# h_bridge.net
KiCad netlist of a schematic drawn in EAGLE
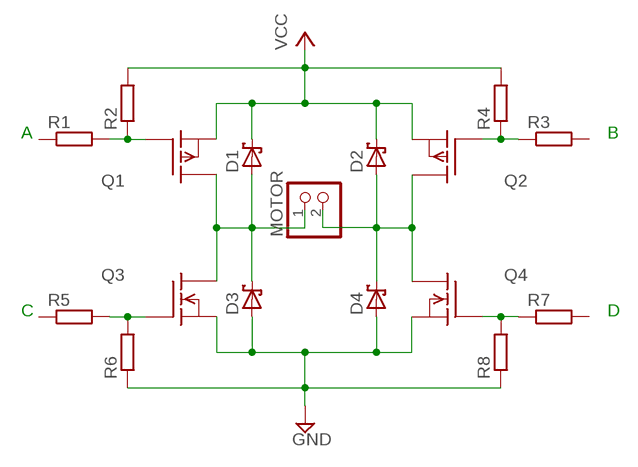
[diagram p0: schematic, sheet 1]

(export (version "E")
  (design (tool "Eeschema 10.0.6"))
  (components
    (comp (ref "D1")
      (value "1N6267A")
      (footprint "eagle-import:C4111-15")
      (libsource (lib "eagle-import") (part "1N6267A"))
    )
    (comp (ref "D2")
      (value "1N6267A")
      (footprint "eagle-import:C4111-15")
      (libsource (lib "eagle-import") (part "1N6267A"))
    )
    (comp (ref "D3")
      (value "1N6267A")
      (footprint "eagle-import:C4111-15")
      (libsource (lib "eagle-import") (part "1N6267A"))
    )
    (comp (ref "D4")
      (value "1N6267A")
      (footprint "eagle-import:C4111-15")
      (libsource (lib "eagle-import") (part "1N6267A"))
    )
    (comp (ref "MOTOR")
      (value "PINHD-1X2")
      (footprint "eagle-import:1X02")
      (libsource (lib "eagle-import") (part "PINHD-1X2"))
    )
    (comp (ref "Q1")
      (value "TP0602N2")
      (footprint "eagle-import:TO-39")
      (libsource (lib "eagle-import") (part "TP0602N2"))
    )
    (comp (ref "Q2")
      (value "TP0602N2")
      (footprint "eagle-import:TO-39")
      (libsource (lib "eagle-import") (part "TP0602N2"))
    )
    (comp (ref "Q3")
      (value "SUP75N06-08")
      (footprint "eagle-import:TO220")
      (libsource (lib "eagle-import") (part "SUP75N06-08"))
    )
    (comp (ref "Q4")
      (value "SUP75N06-08")
      (footprint "eagle-import:TO220")
      (libsource (lib "eagle-import") (part "SUP75N06-08"))
    )
    (comp (ref "R1")
      (value "R-EU_0204/7")
      (footprint "eagle-import:0204_7")
      (libsource (lib "eagle-import") (part "R-EU_0204/7"))
    )
    (comp (ref "R2")
      (value "R-EU_0204/7")
      (footprint "eagle-import:0204_7")
      (libsource (lib "eagle-import") (part "R-EU_0204/7"))
    )
    (comp (ref "R3")
      (value "R-EU_0204/7")
      (footprint "eagle-import:0204_7")
      (libsource (lib "eagle-import") (part "R-EU_0204/7"))
    )
    (comp (ref "R4")
      (value "R-EU_0204/7")
      (footprint "eagle-import:0204_7")
      (libsource (lib "eagle-import") (part "R-EU_0204/7"))
    )
    (comp (ref "R5")
      (value "R-EU_0204/7")
      (footprint "eagle-import:0204_7")
      (libsource (lib "eagle-import") (part "R-EU_0204/7"))
    )
    (comp (ref "R6")
      (value "R-EU_0204/7")
      (footprint "eagle-import:0204_7")
      (libsource (lib "eagle-import") (part "R-EU_0204/7"))
    )
    (comp (ref "R7")
      (value "R-EU_0204/7")
      (footprint "eagle-import:0204_7")
      (libsource (lib "eagle-import") (part "R-EU_0204/7"))
    )
    (comp (ref "R8")
      (value "R-EU_0204/7")
      (footprint "eagle-import:0204_7")
      (libsource (lib "eagle-import") (part "R-EU_0204/7"))
    )
  )
  (nets
    (net (code "1") (name "GND") (class "Default")
      (node (ref "D3") (pin "A") (pinfunction "A_A") (pintype "passive"))
      (node (ref "D4") (pin "A") (pinfunction "A_A") (pintype "passive"))
      (node (ref "Q3") (pin "3") (pinfunction "S_3") (pintype "passive"))
      (node (ref "Q4") (pin "3") (pinfunction "S_3") (pintype "passive"))
      (node (ref "R6") (pin "1") (pinfunction "1_1") (pintype "passive"))
      (node (ref "R8") (pin "1") (pinfunction "1_1") (pintype "passive"))
    )
    (net (code "2") (name "Net-(Q1-D)") (class "Default")
      (node (ref "D1") (pin "A") (pinfunction "A_A") (pintype "passive"))
      (node (ref "D3") (pin "C") (pinfunction "C_C") (pintype "passive"))
      (node (ref "MOTOR") (pin "1") (pinfunction "1_1") (pintype "passive"))
      (node (ref "Q1") (pin "3") (pinfunction "D_3") (pintype "passive"))
      (node (ref "Q3") (pin "2") (pinfunction "D_2") (pintype "passive"))
    )
    (net (code "3") (name "Net-(Q1-G)") (class "Default")
      (node (ref "Q1") (pin "2") (pinfunction "G_2") (pintype "passive"))
      (node (ref "R1") (pin "2") (pinfunction "2_2") (pintype "passive"))
      (node (ref "R2") (pin "1") (pinfunction "1_1") (pintype "passive"))
    )
    (net (code "4") (name "Net-(Q2-D)") (class "Default")
      (node (ref "D2") (pin "A") (pinfunction "A_A") (pintype "passive"))
      (node (ref "D4") (pin "C") (pinfunction "C_C") (pintype "passive"))
      (node (ref "MOTOR") (pin "2") (pinfunction "2_2") (pintype "passive"))
      (node (ref "Q2") (pin "3") (pinfunction "D_3") (pintype "passive"))
      (node (ref "Q4") (pin "2") (pinfunction "D_2") (pintype "passive"))
    )
    (net (code "5") (name "Net-(Q2-G)") (class "Default")
      (node (ref "Q2") (pin "2") (pinfunction "G_2") (pintype "passive"))
      (node (ref "R3") (pin "1") (pinfunction "1_1") (pintype "passive"))
      (node (ref "R4") (pin "1") (pinfunction "1_1") (pintype "passive"))
    )
    (net (code "6") (name "Net-(Q3-G)") (class "Default")
      (node (ref "Q3") (pin "1") (pinfunction "G_1") (pintype "passive"))
      (node (ref "R5") (pin "2") (pinfunction "2_2") (pintype "passive"))
      (node (ref "R6") (pin "2") (pinfunction "2_2") (pintype "passive"))
    )
    (net (code "7") (name "Net-(Q4-G)") (class "Default")
      (node (ref "Q4") (pin "1") (pinfunction "G_1") (pintype "passive"))
      (node (ref "R7") (pin "1") (pinfunction "1_1") (pintype "passive"))
      (node (ref "R8") (pin "2") (pinfunction "2_2") (pintype "passive"))
    )
    (net (code "8") (name "VCC") (class "Default")
      (node (ref "D1") (pin "C") (pinfunction "C_C") (pintype "passive"))
      (node (ref "D2") (pin "C") (pinfunction "C_C") (pintype "passive"))
      (node (ref "Q1") (pin "1") (pinfunction "S_1") (pintype "passive"))
      (node (ref "Q2") (pin "1") (pinfunction "S_1") (pintype "passive"))
      (node (ref "R2") (pin "2") (pinfunction "2_2") (pintype "passive"))
      (node (ref "R4") (pin "2") (pinfunction "2_2") (pintype "passive"))
    )
    (net (code "9") (name "unconnected-(R1-Pad1)") (class "Default")
      (node (ref "R1") (pin "1") (pinfunction "1_1") (pintype "passive"))
    )
    (net (code "10") (name "unconnected-(R3-Pad2)") (class "Default")
      (node (ref "R3") (pin "2") (pinfunction "2_2") (pintype "passive"))
    )
    (net (code "11") (name "unconnected-(R5-Pad1)") (class "Default")
      (node (ref "R5") (pin "1") (pinfunction "1_1") (pintype "passive"))
    )
    (net (code "12") (name "unconnected-(R7-Pad2)") (class "Default")
      (node (ref "R7") (pin "2") (pinfunction "2_2") (pintype "passive"))
    )
  )
)
